# HLib-I2CDevices.net
KiCad netlist of a schematic drawn in Altium Designer
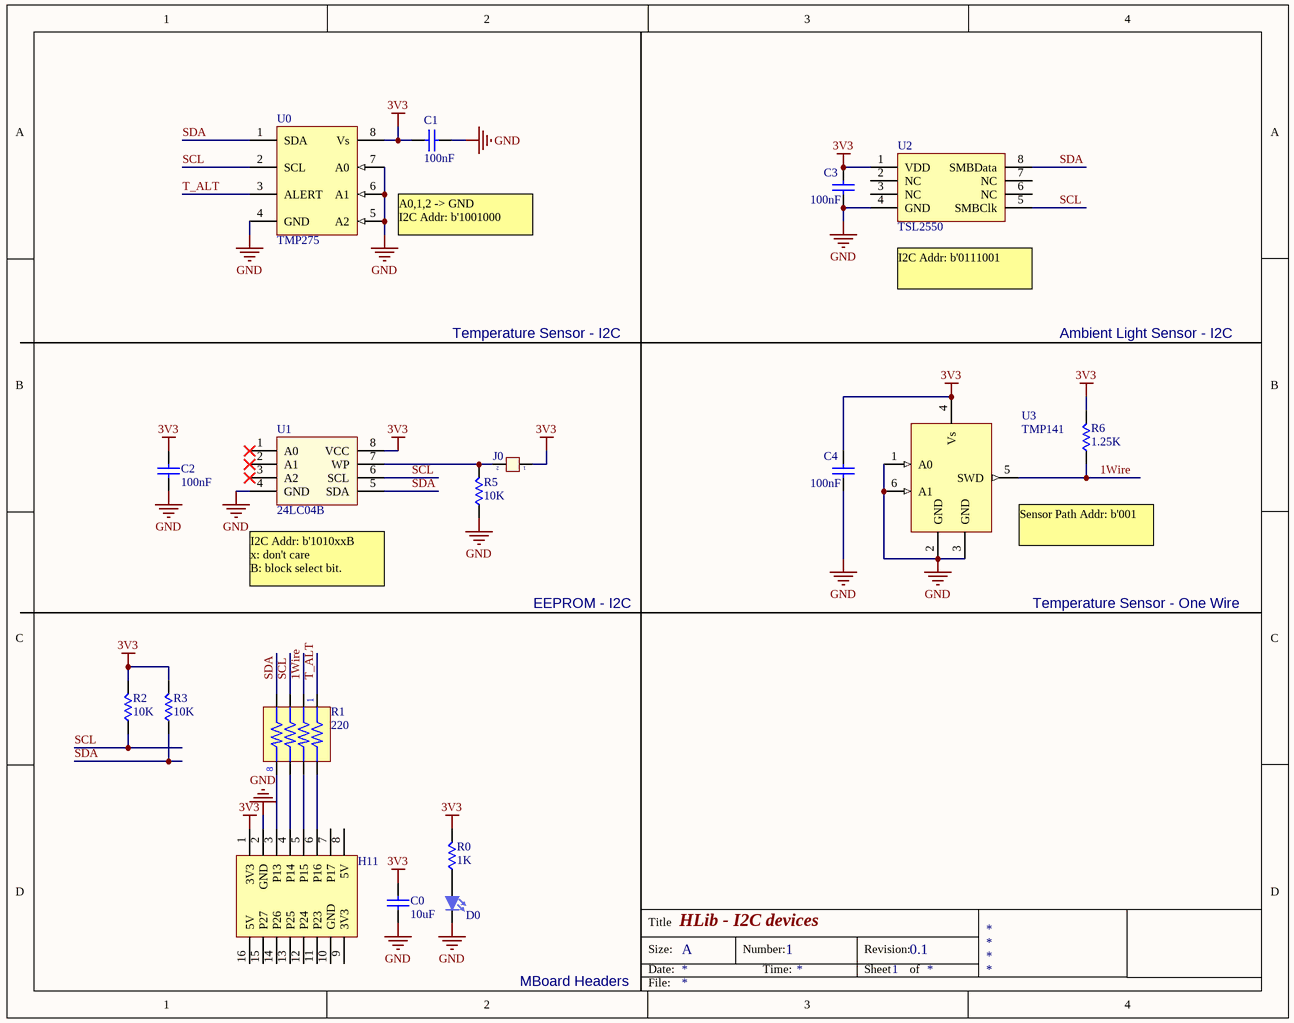
[diagram p0: HLib-I2CDevices.SchDoc]

(export (version "E")
  (design (tool "Eeschema 10.0.6"))
  (components
    (comp (ref "C0")
      (value "10uF")
      (footprint "SM_0805_C_CERAMIC")
      (description "Non-polarity ceramic capacitor")
      (fields (field (name "Comment") "C_Ceramic") (field (name "PUBLISHER") "Altium Limited"))
      (libsource (lib "HLib_discrete_sch") (part "C_Ceramic"))
    )
    (comp (ref "C1")
      (value "100nF")
      (footprint "SM_0805_C_CERAMIC")
      (description "Non-polarity ceramic capacitor")
      (fields (field (name "Comment") "C_Ceramic") (field (name "PUBLISHER") "Altium Limited"))
      (libsource (lib "HLib_discrete_sch") (part "C_Ceramic"))
    )
    (comp (ref "C2")
      (value "100nF")
      (footprint "SM_0805_C_CERAMIC")
      (description "Non-polarity ceramic capacitor")
      (fields (field (name "Comment") "C_Ceramic") (field (name "PUBLISHER") "Altium Limited"))
      (libsource (lib "HLib_discrete_sch") (part "C_Ceramic"))
    )
    (comp (ref "C3")
      (value "100nF")
      (footprint "SM_0805_C_CERAMIC")
      (description "Non-polarity ceramic capacitor")
      (fields (field (name "Comment") "C_Ceramic") (field (name "PUBLISHER") "Altium Limited"))
      (libsource (lib "HLib_discrete_sch") (part "C_Ceramic"))
    )
    (comp (ref "C4")
      (value "100nF")
      (footprint "SM_0805_C_CERAMIC")
      (description "Non-polarity ceramic capacitor")
      (fields (field (name "Comment") "C_Ceramic") (field (name "PUBLISHER") "Altium Limited"))
      (libsource (lib "HLib_discrete_sch") (part "C_Ceramic"))
    )
    (comp (ref "D0")
      (value "LED")
      (footprint "SM_0805_LED")
      (fields (field (name "PUBLISHER") "Altium Limited"))
      (libsource (lib "HLib_discrete_sch") (part "LED"))
    )
    (comp (ref "H11")
      (value "MBoard1_BH_DualPorts")
      (footprint "MBoard1_BH_DualPorts")
      (libsource (lib "Nhat_Lib") (part "MBoard1_BH_DualPorts"))
    )
    (comp (ref "J0")
      (value "Jumper 2")
      (footprint "HD_MALE_2_100mil_straight")
      (libsource (lib "VioletofSun") (part "JP 2"))
    )
    (comp (ref "R0")
      (value "1K")
      (footprint "SM_0805_R")
      (description "Resistor")
      (fields (field (name "Comment") "R") (field (name "PUBLISHER") "Altium Limited"))
      (libsource (lib "HLib_discrete_sch") (part "R"))
    )
    (comp (ref "R1") (value "220") (footprint "RA4") (libsource (lib "Nhat_Lib") (part "RA4")))
    (comp (ref "R2")
      (value "10K")
      (footprint "SM_0805_R")
      (description "Resistor")
      (fields (field (name "Comment") "R") (field (name "PUBLISHER") "Altium Limited"))
      (libsource (lib "HLib_discrete_sch") (part "R"))
    )
    (comp (ref "R3")
      (value "10K")
      (footprint "SM_0805_R")
      (description "Resistor")
      (fields (field (name "Comment") "R") (field (name "PUBLISHER") "Altium Limited"))
      (libsource (lib "HLib_discrete_sch") (part "R"))
    )
    (comp (ref "R5")
      (value "10K")
      (footprint "SM_0805_R")
      (description "Resistor")
      (fields (field (name "Comment") "R") (field (name "PUBLISHER") "Altium Limited"))
      (libsource (lib "HLib_discrete_sch") (part "R"))
    )
    (comp (ref "R6")
      (value "1.25K")
      (footprint "SM_0805_R")
      (description "Resistor")
      (fields (field (name "Comment") "R") (field (name "PUBLISHER") "Altium Limited"))
      (libsource (lib "HLib_discrete_sch") (part "R"))
    )
    (comp (ref "U0") (value "TMP275") (footprint "SO-8") (libsource (lib "Nhat_Lib") (part "TMP75C")))
    (comp (ref "U1")
      (value "24LC04B")
      (footprint "SO-8")
      (description "Standard 2-Wire Bus Interface Serial EEPROM")
      (fields (field (name "COPYRIGHT BY") "VanDungEvn"))
      (libsource (lib "VioletofSun") (part "24Cxx"))
    )
    (comp (ref "U2") (value "TSL2550") (footprint "SO-8") (libsource (lib "Nhat_Lib") (part "TSL2550")))
    (comp (ref "U3") (value "TMP141") (footprint "SOT23-6") (libsource (lib "Nhat_Lib") (part "TMP141")))
  )
  (nets
    (net (code "1") (name "/1Wire") (class "Default")
      (node (ref "R1") (pin "3") (pinfunction "3_3") (pintype "passive"))
      (node (ref "R6") (pin "1") (pinfunction "1_1") (pintype "passive"))
      (node (ref "U3") (pin "5") (pinfunction "SWD_5") (pintype "output"))
    )
    (net (code "2") (name "/SCL") (class "Default")
      (node (ref "R1") (pin "5") (pinfunction "5_5") (pintype "passive"))
      (node (ref "R2") (pin "1") (pinfunction "1_1") (pintype "passive"))
      (node (ref "U0") (pin "2") (pinfunction "SCL_2") (pintype "open_collector"))
      (node (ref "U1") (pin "6") (pinfunction "SCL_6") (pintype "passive"))
      (node (ref "U2") (pin "5") (pinfunction "SMBClk_5") (pintype "passive"))
    )
    (net (code "3") (name "/SDA") (class "Default")
      (node (ref "R1") (pin "7") (pinfunction "7_7") (pintype "passive"))
      (node (ref "R3") (pin "1") (pinfunction "1_1") (pintype "passive"))
      (node (ref "U0") (pin "1") (pinfunction "SDA_1") (pintype "open_collector"))
      (node (ref "U1") (pin "5") (pinfunction "SDA_5") (pintype "passive"))
      (node (ref "U2") (pin "8") (pinfunction "SMBData_8") (pintype "passive"))
    )
    (net (code "4") (name "/T_ALT") (class "Default")
      (node (ref "R1") (pin "1") (pinfunction "1_1") (pintype "passive"))
      (node (ref "U0") (pin "3") (pinfunction "ALERT_3") (pintype "open_collector"))
    )
    (net (code "5") (name "3V3") (class "Default")
      (node (ref "C0") (pin "2") (pinfunction "2_2") (pintype "passive"))
      (node (ref "C1") (pin "2") (pinfunction "2_2") (pintype "passive"))
      (node (ref "C2") (pin "1") (pinfunction "1_1") (pintype "passive"))
      (node (ref "C3") (pin "1") (pinfunction "1_1") (pintype "passive"))
      (node (ref "C4") (pin "1") (pinfunction "1_1") (pintype "passive"))
      (node (ref "H11") (pin "1") (pinfunction "3V3_1") (pintype "passive"))
      (node (ref "J0") (pin "1") (pinfunction "1_1") (pintype "passive"))
      (node (ref "R0") (pin "2") (pinfunction "2_2") (pintype "passive"))
      (node (ref "R2") (pin "2") (pinfunction "2_2") (pintype "passive"))
      (node (ref "R3") (pin "2") (pinfunction "2_2") (pintype "passive"))
      (node (ref "R6") (pin "2") (pinfunction "2_2") (pintype "passive"))
      (node (ref "U0") (pin "8") (pinfunction "Vs_8") (pintype "power_in"))
      (node (ref "U1") (pin "8") (pinfunction "VCC_8") (pintype "power_in"))
      (node (ref "U2") (pin "1") (pinfunction "VDD_1") (pintype "power_in"))
      (node (ref "U3") (pin "4") (pinfunction "Vs_4") (pintype "power_in"))
    )
    (net (code "6") (name "GND") (class "Default")
      (node (ref "C0") (pin "1") (pinfunction "1_1") (pintype "passive"))
      (node (ref "C1") (pin "1") (pinfunction "1_1") (pintype "passive"))
      (node (ref "C2") (pin "2") (pinfunction "2_2") (pintype "passive"))
      (node (ref "C3") (pin "2") (pinfunction "2_2") (pintype "passive"))
      (node (ref "C4") (pin "2") (pinfunction "2_2") (pintype "passive"))
      (node (ref "D0") (pin "2") (pinfunction "K_2") (pintype "passive"))
      (node (ref "H11") (pin "2") (pinfunction "GND_2") (pintype "passive"))
      (node (ref "R5") (pin "1") (pinfunction "1_1") (pintype "passive"))
      (node (ref "U0") (pin "4") (pinfunction "GND_4") (pintype "passive"))
      (node (ref "U0") (pin "5") (pinfunction "A2_5") (pintype "input"))
      (node (ref "U0") (pin "6") (pinfunction "A1_6") (pintype "input"))
      (node (ref "U0") (pin "7") (pinfunction "A0_7") (pintype "input"))
      (node (ref "U1") (pin "4") (pinfunction "GND_4") (pintype "power_in"))
      (node (ref "U2") (pin "4") (pinfunction "GND_4") (pintype "passive"))
      (node (ref "U3") (pin "1") (pinfunction "A0_1") (pintype "input"))
      (node (ref "U3") (pin "2") (pinfunction "GND_2") (pintype "power_in"))
      (node (ref "U3") (pin "3") (pinfunction "GND_3") (pintype "power_in"))
      (node (ref "U3") (pin "6") (pinfunction "A1_6") (pintype "input"))
    )
    (net (code "7") (name "Net-(D0-A)") (class "Default")
      (node (ref "D0") (pin "1") (pinfunction "A_1") (pintype "passive"))
      (node (ref "R0") (pin "1") (pinfunction "1_1") (pintype "passive"))
    )
    (net (code "8") (name "Net-(H11-P13)") (class "Default")
      (node (ref "H11") (pin "3") (pinfunction "P13_3") (pintype "passive"))
      (node (ref "R1") (pin "8") (pinfunction "8_8") (pintype "passive"))
    )
    (net (code "9") (name "Net-(H11-P14)") (class "Default")
      (node (ref "H11") (pin "4") (pinfunction "P14_4") (pintype "passive"))
      (node (ref "R1") (pin "6") (pinfunction "6_6") (pintype "passive"))
    )
    (net (code "10") (name "Net-(H11-P15)") (class "Default")
      (node (ref "H11") (pin "5") (pinfunction "P15_5") (pintype "passive"))
      (node (ref "R1") (pin "4") (pinfunction "4_4") (pintype "passive"))
    )
    (net (code "11") (name "Net-(H11-P16)") (class "Default")
      (node (ref "H11") (pin "6") (pinfunction "P16_6") (pintype "passive"))
      (node (ref "R1") (pin "2") (pinfunction "2_2") (pintype "passive"))
    )
    (net (code "12") (name "Net-(U1-WP)") (class "Default")
      (node (ref "J0") (pin "2") (pinfunction "2_2") (pintype "passive"))
      (node (ref "R5") (pin "2") (pinfunction "2_2") (pintype "passive"))
      (node (ref "U1") (pin "7") (pinfunction "WP_7") (pintype "passive"))
    )
    (net (code "13") (name "unconnected-(H11-3V3-Pad9)") (class "Default")
      (node (ref "H11") (pin "9") (pinfunction "3V3_9") (pintype "passive"))
    )
    (net (code "14") (name "unconnected-(H11-5V-Pad8)") (class "Default")
      (node (ref "H11") (pin "8") (pinfunction "5V_8") (pintype "passive"))
    )
    (net (code "15") (name "unconnected-(H11-5V-Pad16)") (class "Default")
      (node (ref "H11") (pin "16") (pinfunction "5V_16") (pintype "passive"))
    )
    (net (code "16") (name "unconnected-(H11-GND-Pad10)") (class "Default")
      (node (ref "H11") (pin "10") (pinfunction "GND_10") (pintype "passive"))
    )
    (net (code "17") (name "unconnected-(H11-P17-Pad7)") (class "Default")
      (node (ref "H11") (pin "7") (pinfunction "P17_7") (pintype "passive"))
    )
    (net (code "18") (name "unconnected-(H11-P23-Pad11)") (class "Default")
      (node (ref "H11") (pin "11") (pinfunction "P23_11") (pintype "passive"))
    )
    (net (code "19") (name "unconnected-(H11-P24-Pad12)") (class "Default")
      (node (ref "H11") (pin "12") (pinfunction "P24_12") (pintype "passive"))
    )
    (net (code "20") (name "unconnected-(H11-P25-Pad13)") (class "Default")
      (node (ref "H11") (pin "13") (pinfunction "P25_13") (pintype "passive"))
    )
    (net (code "21") (name "unconnected-(H11-P26-Pad14)") (class "Default")
      (node (ref "H11") (pin "14") (pinfunction "P26_14") (pintype "passive"))
    )
    (net (code "22") (name "unconnected-(H11-P27-Pad15)") (class "Default")
      (node (ref "H11") (pin "15") (pinfunction "P27_15") (pintype "passive"))
    )
    (net (code "23") (name "unconnected-(U1-A0-Pad1)") (class "Default")
      (node (ref "U1") (pin "1") (pinfunction "A0_1") (pintype "passive+no_connect"))
    )
    (net (code "24") (name "unconnected-(U1-A1-Pad2)") (class "Default")
      (node (ref "U1") (pin "2") (pinfunction "A1_2") (pintype "passive+no_connect"))
    )
    (net (code "25") (name "unconnected-(U1-A2-Pad3)") (class "Default")
      (node (ref "U1") (pin "3") (pinfunction "A2_3") (pintype "passive+no_connect"))
    )
    (net (code "26") (name "unconnected-(U2-NC-Pad2)") (class "Default")
      (node (ref "U2") (pin "2") (pinfunction "NC_2") (pintype "passive"))
    )
    (net (code "27") (name "unconnected-(U2-NC-Pad3)") (class "Default")
      (node (ref "U2") (pin "3") (pinfunction "NC_3") (pintype "passive"))
    )
    (net (code "28") (name "unconnected-(U2-NC-Pad6)") (class "Default")
      (node (ref "U2") (pin "6") (pinfunction "NC_6") (pintype "passive"))
    )
    (net (code "29") (name "unconnected-(U2-NC-Pad7)") (class "Default")
      (node (ref "U2") (pin "7") (pinfunction "NC_7") (pintype "passive"))
    )
  )
)
